# Power.net
KiCad netlist of a schematic drawn in Altium Designer
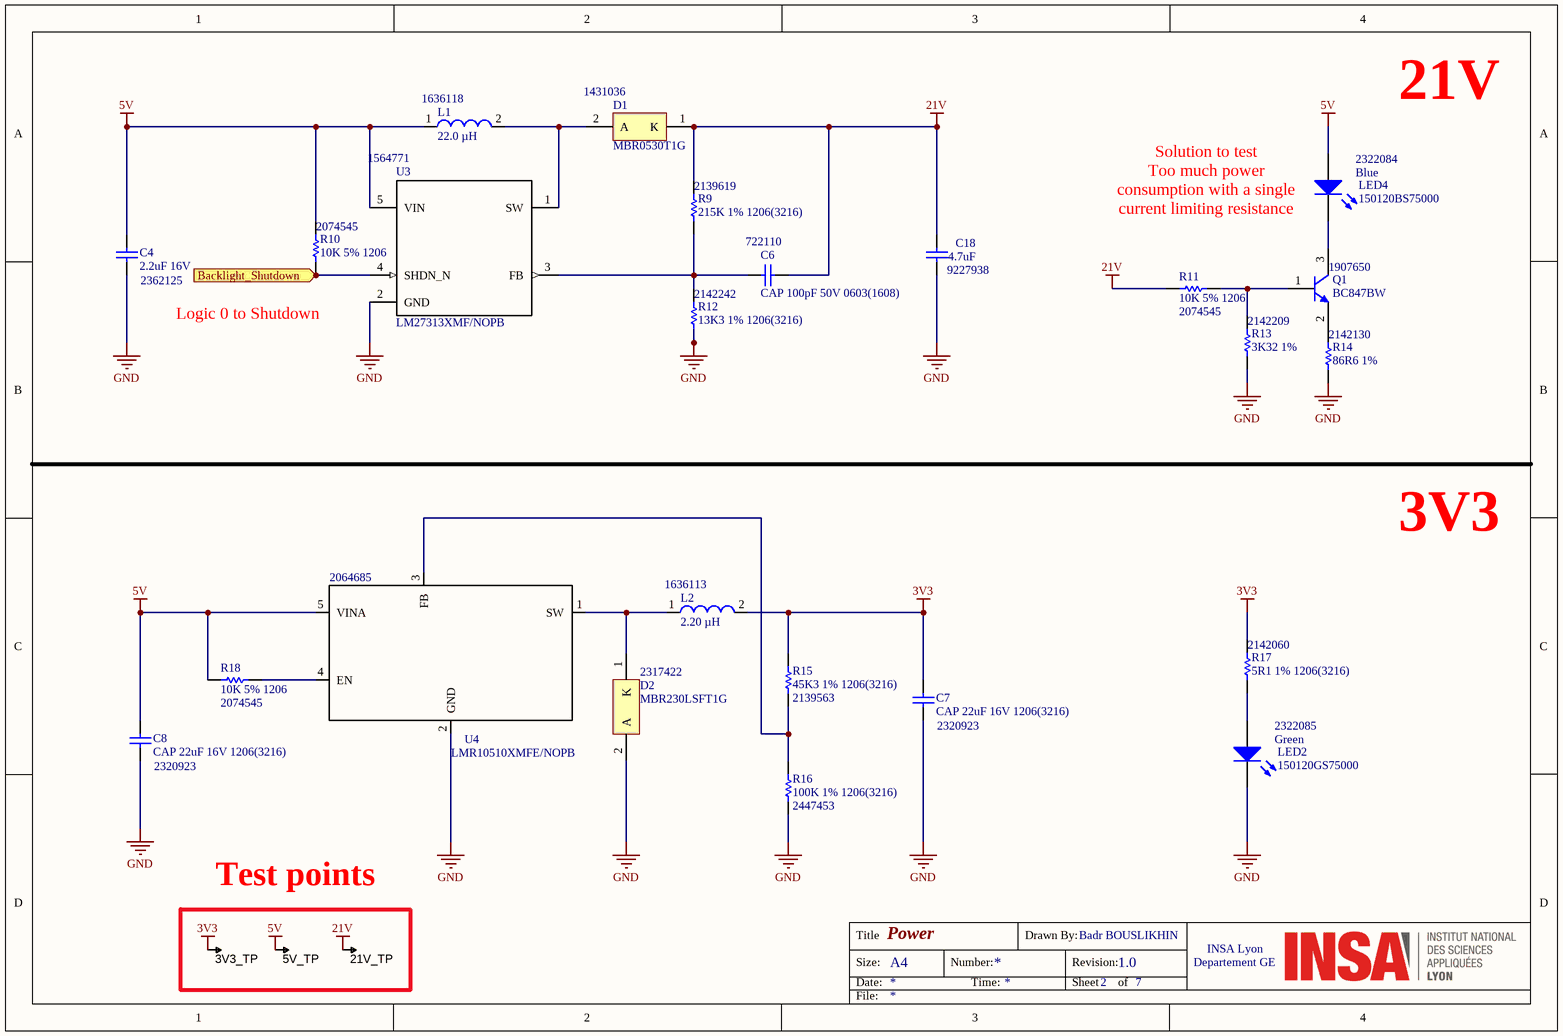
[diagram p0: Power.SchDoc]

(export (version "E")
  (design (tool "Eeschema 10.0.6"))
  (components
    (comp (ref "3V3_TP")
      (value "TESTPOINT")
      (footprint "TP-R60")
      (description "SMD test pin")
      (libsource (lib "PBL - Test Points") (part "TESTPOINT"))
    )
    (comp (ref "5V_TP")
      (value "TESTPOINT")
      (footprint "TP-R60")
      (description "SMD test pin")
      (libsource (lib "PBL - Test Points") (part "TESTPOINT"))
    )
    (comp (ref "21V_TP")
      (value "TESTPOINT")
      (footprint "TP-R60")
      (description "SMD test pin")
      (libsource (lib "PBL - Test Points") (part "TESTPOINT"))
    )
    (comp (ref "C4")
      (value "2.2uF 16V")
      (footprint "CAPC1206(3216)190_L")
      (description "CAP 2.2uF 16V ±20% 1206 (3216 Metric) Thickness 1.9mm SMD")
      (fields (field (name "TOLERANCE") "±20%") (field (name "SUPPLIER PART NUMBER 1") "2362125"))
      (libsource (lib "Altium Content Vault") (part "CMP-1037-04816-1"))
    )
    (comp (ref "C6")
      (value "CAP 100pF 50V 0603(1608)")
      (footprint "CAPC0603(1608)100_L")
      (description "CAP 100pF 50V ±10% 0603 (1608 Metric) Thickness 1mm SMD")
      (fields
        (field (name "TOLERANCE") "±10%")
        (field (name "SUPPLIER PART NUMBER 1") "722110")
        (field (name "MANUFACTURER") "YAGEO (PHYCOMP)")
      )
      (libsource (lib "Altium Content Vault") (part "CAP"))
    )
    (comp (ref "C7")
      (value "CAP 22uF 16V 1206(3216)")
      (footprint "CAPC1206(3216)190_N")
      (description "CAP 22uF 16V ±10% 1206 (3216 Metric) Thickness 1.9mm SMD")
      (fields (field (name "TOLERANCE") "±10%") (field (name "SUPPLIER PART NUMBER 1") "2320923"))
      (libsource (lib "Altium Content Vault") (part "CMP-1037-04992-1"))
    )
    (comp (ref "C8")
      (value "CAP 22uF 16V 1206(3216)")
      (footprint "CAPC1206(3216)190_N")
      (description "CAP 22uF 16V ±10% 1206 (3216 Metric) Thickness 1.9mm SMD")
      (fields (field (name "TOLERANCE") "±10%") (field (name "SUPPLIER PART NUMBER 1") "2320923"))
      (libsource (lib "Altium Content Vault") (part "CMP-1037-04992-1"))
    )
    (comp (ref "C18")
      (value "4.7uF")
      (footprint "CAPC1206(3216)190_N")
      (description "CAP 4.7uF 50V ±10% 1206 (3216 Metric) Thickness 1.9mm SMD")
      (fields (field (name "TOLERANCE") "±10%") (field (name "SUPPLIER PART NUMBER 1") "9227938"))
      (libsource (lib "Altium Content Vault") (part "CAP"))
    )
    (comp (ref "D1")
      (value "MBR0530T1G")
      (footprint "ONSC-SOD-123-2-425-04_V")
      (description "Schottky Power Rectifier, 2-Pin SOD-123, Pb-Free, Tape and Reel")
      (fields
        (field (name "MANUFACTURER") "On Semiconductor")
        (field (name "SUPPLIER PART NUMBER 1") "1431036")
      )
      (libsource (lib "Altium Content Vault") (part "CMP-1055-00413-1"))
    )
    (comp (ref "D2")
      (value "MBR230LSFT1G")
      (footprint "ONSC-SOD-123FL-2-498-01_V")
      (description "Schottky Power Rectifier, 2-Pin SOD-123, Pb-Free, Tape and Reel")
      (fields
        (field (name "MANUFACTURER") "On Semiconductor")
        (field (name "SUPPLIER PART NUMBER 1") "2317422")
      )
      (libsource (lib "Altium Content Vault") (part "CMP-1055-00442-1"))
    )
    (comp (ref "L1")
      (value "22.0 µH")
      (footprint "WE-PD4-S")
      (description "SMD-Power Inductor WE-PD4, L = 22.0 µH")
      (fields (field (name "SUPPLIER PART NUMBER 1") "1636118"))
      (libsource (lib "Altium Content Vault") (part "CMP-0227-00739-1"))
    )
    (comp (ref "L2")
      (value "2.20 µH")
      (footprint "WE-PD4-S")
      (description "SMD-Power Inductor WE-PD4, L = 2.20 µH")
      (fields
        (field (name "SUPPLIER PART NUMBER 1") "1636113")
        (field (name "MANUFACTURER") "WURTH ELEKTRONIK")
        (field (name "MANUFACTURER PART NUMBER") "74455022")
      )
      (libsource (lib "Altium Content Vault") (part "CMP-0227-00671-1"))
    )
    (comp (ref "LED2")
      (value "150120GS75000")
      (footprint "1206_A")
      (description "SMD mono-color Chip LED, WL-SMCW, Green")
      (fields
        (field (name "MANUFACTURER") "Wuerth Elektronik")
        (field (name "COLOR") "Green")
        (field (name "SUPPLIER PART NUMBER 1") "2322085")
      )
      (libsource (lib "Altium Content Vault") (part "CMP-1426-00014-1"))
    )
    (comp (ref "LED4")
      (value "150120BS75000")
      (footprint "1206_A")
      (description "SMD mono-color Chip LED, WL-SMCW, Blue")
      (fields
        (field (name "MANUFACTURER") "Wuerth Elektronik")
        (field (name "COLOR") "Blue")
        (field (name "SUPPLIER PART NUMBER 1") "2322084")
      )
      (libsource (lib "Altium Content Vault") (part "CMP-1426-00015-1"))
    )
    (comp (ref "Q1")
      (value "BC847BW")
      (footprint "INF-SOT323_N")
      (description "NPN Silicon AF Transistor, 45 V VCEO, 100 mA IC, SOT323, Reel, Green")
      (fields (field (name "MANUFACTURER") "Infineon") (field (name "SUPPLIER PART NUMBER 1") "1907650"))
      (libsource (lib "Altium Content Vault") (part "INF-BJTNPN-BEC-3"))
    )
    (comp (ref "R9")
      (value "215K 1% 1206(3216)")
      (footprint "RESC1206(3216)_M")
      (description "215K 0.25W 1% 1206 (3216 Metric)  SMD")
      (fields
        (field (name "TOLERANCE") "1 %")
        (field (name "POWER") "0.25 W")
        (field (name "SUPPLIER PART NUMBER 1") "2139619")
      )
      (libsource (lib "Altium Content Vault") (part "RES"))
    )
    (comp (ref "R10")
      (value "10K 5% 1206")
      (footprint "RESC1206(3216)_M")
      (description "10K 0.25W 5% 1206 (3216 Metric)  SMD")
      (fields
        (field (name "POWER") "0.25 W")
        (field (name "TOLERANCE") "5 %")
        (field (name "SUPPLIER PART NUMBER 1") "2074545")
      )
      (libsource (lib "Altium Content Vault") (part "CMP-1014-00098-1"))
    )
    (comp (ref "R11")
      (value "10K 5% 1206")
      (footprint "RESC1206(3216)_M")
      (description "10K 0.25W 5% 1206 (3216 Metric)  SMD")
      (fields
        (field (name "POWER") "0.25 W")
        (field (name "TOLERANCE") "5 %")
        (field (name "SUPPLIER PART NUMBER 1") "2074545")
      )
      (libsource (lib "Altium Content Vault") (part "CMP-1014-00098-1"))
    )
    (comp (ref "R12")
      (value "13K3 1% 1206(3216)")
      (footprint "RESC1206(3216)_L")
      (description "13K3 0.25W 1% 1206 (3216 Metric)  SMD")
      (fields
        (field (name "TOLERANCE") "1 %")
        (field (name "POWER") "0.25 W")
        (field (name "SUPPLIER PART NUMBER 1") "2142242")
      )
      (libsource (lib "Altium Content Vault") (part "RES"))
    )
    (comp (ref "R13")
      (value "3K32 1%")
      (footprint "RESC1206(3216)_L")
      (description "3K32 0.25W 1% 1206 (3216 Metric)  SMD")
      (fields
        (field (name "TOLERANCE") "1 %")
        (field (name "POWER") "0.25 W")
        (field (name "SUPPLIER PART NUMBER 1") "2142209")
      )
      (libsource (lib "Altium Content Vault") (part "RES"))
    )
    (comp (ref "R14")
      (value "86R6 1%")
      (footprint "RESC1206(3216)_N")
      (description "86R6 0.25W 1% 1206 (3216 Metric)  SMD")
      (fields
        (field (name "TOLERANCE") "1 %")
        (field (name "POWER") "0.25 W")
        (field (name "SUPPLIER PART NUMBER 1") "2142130")
      )
      (libsource (lib "Altium Content Vault") (part "RES"))
    )
    (comp (ref "R15")
      (value "45K3 1% 1206(3216)")
      (footprint "RESC1206(3216)_L")
      (description "45K3 0.25W 1% 1206 (3216 Metric)  SMD")
      (fields
        (field (name "TOLERANCE") "1 %")
        (field (name "POWER") "0.25 W")
        (field (name "SUPPLIER PART NUMBER 1") "2139563")
      )
      (libsource (lib "Altium Content Vault") (part "RES"))
    )
    (comp (ref "R16")
      (value "100K 1% 1206(3216)")
      (footprint "RESC1206(3216)_L")
      (description "100K 0.25W 1% 1206 (3216 Metric)  SMD")
      (fields
        (field (name "TOLERANCE") "1 %")
        (field (name "POWER") "0.25 W")
        (field (name "SUPPLIER PART NUMBER 1") "2447453")
      )
      (libsource (lib "Altium Content Vault") (part "RES"))
    )
    (comp (ref "R17")
      (value "5R1 1% 1206(3216)")
      (footprint "RESC1206(3216)_N")
      (description "5R1 0.25W 1% 1206 (3216 Metric)  SMD")
      (fields
        (field (name "TOLERANCE") "1 %")
        (field (name "POWER") "0.25 W")
        (field (name "SUPPLIER PART NUMBER 1") "2142060")
      )
      (libsource (lib "Altium Content Vault") (part "RES"))
    )
    (comp (ref "R18")
      (value "10K 5% 1206")
      (footprint "RESC1206(3216)_M")
      (description "10K 0.25W 5% 1206 (3216 Metric)  SMD")
      (fields
        (field (name "POWER") "0.25 W")
        (field (name "TOLERANCE") "5 %")
        (field (name "SUPPLIER PART NUMBER 1") "2074545")
      )
      (libsource (lib "Altium Content Vault") (part "CMP-1014-00098-1"))
    )
    (comp (ref "U3")
      (value "LM27313XMF/NOPB")
      (footprint "DBV0005A")
      (description "Imported")
      (fields
        (field (name "PARTNUMBER") "LM27313XQMF/NOPB")
        (field (name "MANUFACTURER") "Texas Instruments")
        (field (name "SUPPLIER PART NUMBER 1") "1564771")
      )
      (libsource (lib "LM27313") (part "LM27313XMF/NOPB"))
    )
    (comp (ref "U4")
      (value "LMR10510XMFE/NOPB")
      (footprint "DBV0005A")
      (description "Imported")
      (fields
        (field (name "SUPPLIER PART NUMBER 1") "2064685")
        (field (name "MANUFACTURER") "TEXAS INSTRUMENTS")
        (field (name "MANUFACTURER PART NUMBER") "LMR10510XMF")
      )
      (libsource (lib "LMR10510") (part "LMR10510XMFE/NOPB"))
    )
  )
  (nets
    (net (code "1") (name "/Backlight_Shutdown") (class "Default")
      (node (ref "R10") (pin "1") (pinfunction "1_1") (pintype "passive"))
      (node (ref "U3") (pin "4") (pinfunction "SHDN_N_4") (pintype "input"))
    )
    (net (code "2") (name "3V3") (class "Default")
      (node (ref "3V3_TP") (pin "1") (pintype "passive"))
      (node (ref "C7") (pin "2") (pinfunction "2_2") (pintype "passive"))
      (node (ref "L2") (pin "2") (pinfunction "2_2") (pintype "passive"))
      (node (ref "R15") (pin "1") (pinfunction "1_1") (pintype "passive"))
      (node (ref "R17") (pin "2") (pinfunction "2_2") (pintype "passive"))
    )
    (net (code "3") (name "5V") (class "Default")
      (node (ref "5V_TP") (pin "1") (pintype "passive"))
      (node (ref "C4") (pin "2") (pinfunction "2_2") (pintype "passive"))
      (node (ref "C8") (pin "2") (pinfunction "2_2") (pintype "passive"))
      (node (ref "L1") (pin "1") (pinfunction "1_1") (pintype "passive"))
      (node (ref "LED4") (pin "2") (pinfunction "A_2") (pintype "passive"))
      (node (ref "R10") (pin "2") (pinfunction "2_2") (pintype "passive"))
      (node (ref "R18") (pin "2") (pinfunction "2_2") (pintype "passive"))
      (node (ref "U3") (pin "5") (pinfunction "VIN_5") (pintype "power_in"))
      (node (ref "U4") (pin "5") (pinfunction "VINA_5") (pintype "passive"))
    )
    (net (code "4") (name "21V") (class "Default")
      (node (ref "21V_TP") (pin "1") (pintype "passive"))
      (node (ref "C18") (pin "2") (pinfunction "2_2") (pintype "passive"))
      (node (ref "C6") (pin "2") (pinfunction "2_2") (pintype "passive"))
      (node (ref "D1") (pin "1") (pinfunction "K_1") (pintype "passive"))
      (node (ref "R11") (pin "2") (pinfunction "2_2") (pintype "passive"))
      (node (ref "R9") (pin "2") (pinfunction "2_2") (pintype "passive"))
    )
    (net (code "5") (name "GND") (class "Default")
      (node (ref "C18") (pin "1") (pinfunction "1_1") (pintype "passive"))
      (node (ref "C4") (pin "1") (pinfunction "1_1") (pintype "passive"))
      (node (ref "C7") (pin "1") (pinfunction "1_1") (pintype "passive"))
      (node (ref "C8") (pin "1") (pinfunction "1_1") (pintype "passive"))
      (node (ref "D2") (pin "2") (pinfunction "A_2") (pintype "passive"))
      (node (ref "LED2") (pin "1") (pinfunction "K_1") (pintype "passive"))
      (node (ref "R12") (pin "1") (pinfunction "1_1") (pintype "passive"))
      (node (ref "R13") (pin "1") (pinfunction "1_1") (pintype "passive"))
      (node (ref "R14") (pin "1") (pinfunction "1_1") (pintype "passive"))
      (node (ref "R16") (pin "1") (pinfunction "1_1") (pintype "passive"))
      (node (ref "U3") (pin "2") (pinfunction "GND_2") (pintype "power_in"))
      (node (ref "U4") (pin "2") (pinfunction "GND_2") (pintype "passive"))
    )
    (net (code "6") (name "Net-(D1-A)") (class "Default")
      (node (ref "D1") (pin "2") (pinfunction "A_2") (pintype "passive"))
      (node (ref "L1") (pin "2") (pinfunction "2_2") (pintype "passive"))
      (node (ref "U3") (pin "1") (pinfunction "SW_1") (pintype "power_in"))
    )
    (net (code "7") (name "Net-(D2-K)") (class "Default")
      (node (ref "D2") (pin "1") (pinfunction "K_1") (pintype "passive"))
      (node (ref "L2") (pin "1") (pinfunction "1_1") (pintype "passive"))
      (node (ref "U4") (pin "1") (pinfunction "SW_1") (pintype "passive"))
    )
    (net (code "8") (name "Net-(LED2-A)") (class "Default")
      (node (ref "LED2") (pin "2") (pinfunction "A_2") (pintype "passive"))
      (node (ref "R17") (pin "1") (pinfunction "1_1") (pintype "passive"))
    )
    (net (code "9") (name "Net-(LED4-K)") (class "Default")
      (node (ref "LED4") (pin "1") (pinfunction "K_1") (pintype "passive"))
      (node (ref "Q1") (pin "3") (pinfunction "C_3") (pintype "passive"))
    )
    (net (code "10") (name "Net-(Q1-B)") (class "Default")
      (node (ref "Q1") (pin "1") (pinfunction "B_1") (pintype "passive"))
      (node (ref "R11") (pin "1") (pinfunction "1_1") (pintype "passive"))
      (node (ref "R13") (pin "2") (pinfunction "2_2") (pintype "passive"))
    )
    (net (code "11") (name "Net-(Q1-E)") (class "Default")
      (node (ref "Q1") (pin "2") (pinfunction "E_2") (pintype "passive"))
      (node (ref "R14") (pin "2") (pinfunction "2_2") (pintype "passive"))
    )
    (net (code "12") (name "Net-(U3-FB)") (class "Default")
      (node (ref "C6") (pin "1") (pinfunction "1_1") (pintype "passive"))
      (node (ref "R12") (pin "2") (pinfunction "2_2") (pintype "passive"))
      (node (ref "R9") (pin "1") (pinfunction "1_1") (pintype "passive"))
      (node (ref "U3") (pin "3") (pinfunction "FB_3") (pintype "output"))
    )
    (net (code "13") (name "Net-(U4-EN)") (class "Default")
      (node (ref "R18") (pin "1") (pinfunction "1_1") (pintype "passive"))
      (node (ref "U4") (pin "4") (pinfunction "EN_4") (pintype "passive"))
    )
    (net (code "14") (name "Net-(U4-FB)") (class "Default")
      (node (ref "R15") (pin "2") (pinfunction "2_2") (pintype "passive"))
      (node (ref "R16") (pin "2") (pinfunction "2_2") (pintype "passive"))
      (node (ref "U4") (pin "3") (pinfunction "FB_3") (pintype "passive"))
    )
  )
)
